# Ornament.net
KiCad netlist of a schematic drawn in Altium Designer
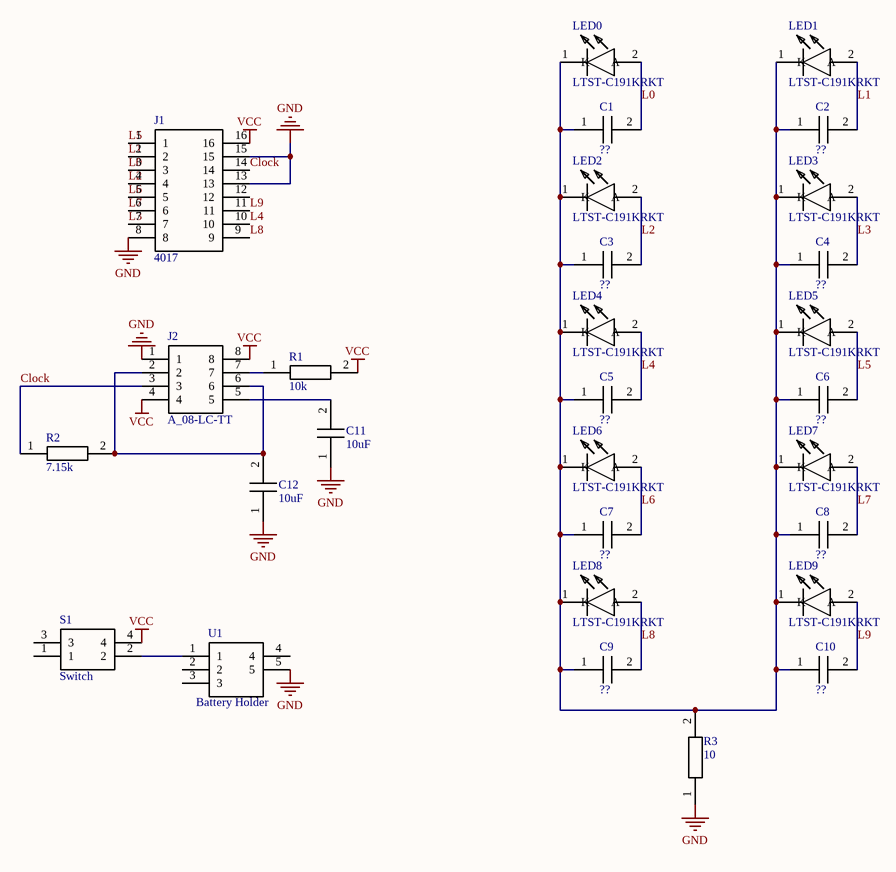
[diagram p0: Ornament.SchDoc]

(export (version "E")
  (design (tool "Eeschema 10.0.6"))
  (components
    (comp (ref "C1")
      (value "??")
      (footprint "SamacSys:CAPC2013X140N")
      (description "Capacitor")
      (fields
        (field (name "MANUFACTURER_PART_NUMBER") "C0805C106K8PACTU")
        (field (name "MOUSER PART NUMBER") "80-C0805C106K8P")
      )
      (libsource (lib "*") (part "C0805C106K8PACTU"))
    )
    (comp (ref "C2")
      (value "??")
      (footprint "SamacSys:CAPC2013X140N")
      (description "Capacitor")
      (fields
        (field (name "MANUFACTURER_PART_NUMBER") "C0805C106K8PACTU")
        (field (name "MOUSER PART NUMBER") "80-C0805C106K8P")
      )
      (libsource (lib "*") (part "C0805C106K8PACTU"))
    )
    (comp (ref "C3")
      (value "??")
      (footprint "SamacSys:CAPC2013X140N")
      (description "Capacitor")
      (fields
        (field (name "MANUFACTURER_PART_NUMBER") "C0805C106K8PACTU")
        (field (name "MOUSER PART NUMBER") "80-C0805C106K8P")
      )
      (libsource (lib "*") (part "C0805C106K8PACTU"))
    )
    (comp (ref "C4")
      (value "??")
      (footprint "SamacSys:CAPC2013X140N")
      (description "Capacitor")
      (fields
        (field (name "MANUFACTURER_PART_NUMBER") "C0805C106K8PACTU")
        (field (name "MOUSER PART NUMBER") "80-C0805C106K8P")
      )
      (libsource (lib "*") (part "C0805C106K8PACTU"))
    )
    (comp (ref "C5")
      (value "??")
      (footprint "SamacSys:CAPC2013X140N")
      (description "Capacitor")
      (fields
        (field (name "MANUFACTURER_PART_NUMBER") "C0805C106K8PACTU")
        (field (name "MOUSER PART NUMBER") "80-C0805C106K8P")
      )
      (libsource (lib "*") (part "C0805C106K8PACTU"))
    )
    (comp (ref "C6")
      (value "??")
      (footprint "SamacSys:CAPC2013X140N")
      (description "Capacitor")
      (fields
        (field (name "MANUFACTURER_PART_NUMBER") "C0805C106K8PACTU")
        (field (name "MOUSER PART NUMBER") "80-C0805C106K8P")
      )
      (libsource (lib "*") (part "C0805C106K8PACTU"))
    )
    (comp (ref "C7")
      (value "??")
      (footprint "SamacSys:CAPC2013X140N")
      (description "Capacitor")
      (fields
        (field (name "MANUFACTURER_PART_NUMBER") "C0805C106K8PACTU")
        (field (name "MOUSER PART NUMBER") "80-C0805C106K8P")
      )
      (libsource (lib "*") (part "C0805C106K8PACTU"))
    )
    (comp (ref "C8")
      (value "??")
      (footprint "SamacSys:CAPC2013X140N")
      (description "Capacitor")
      (fields
        (field (name "MANUFACTURER_PART_NUMBER") "C0805C106K8PACTU")
        (field (name "MOUSER PART NUMBER") "80-C0805C106K8P")
      )
      (libsource (lib "*") (part "C0805C106K8PACTU"))
    )
    (comp (ref "C9")
      (value "??")
      (footprint "SamacSys:CAPC2013X140N")
      (description "Capacitor")
      (fields
        (field (name "MANUFACTURER_PART_NUMBER") "C0805C106K8PACTU")
        (field (name "MOUSER PART NUMBER") "80-C0805C106K8P")
      )
      (libsource (lib "*") (part "C0805C106K8PACTU"))
    )
    (comp (ref "C10")
      (value "??")
      (footprint "SamacSys:CAPC2013X140N")
      (description "Capacitor")
      (fields
        (field (name "MANUFACTURER_PART_NUMBER") "C0805C106K8PACTU")
        (field (name "MOUSER PART NUMBER") "80-C0805C106K8P")
      )
      (libsource (lib "*") (part "C0805C106K8PACTU"))
    )
    (comp (ref "C11")
      (value "10uF")
      (footprint "SamacSys:CAPC2013X140N")
      (description "Capacitor")
      (fields
        (field (name "MANUFACTURER_PART_NUMBER") "C0805C106K8PACTU")
        (field (name "MOUSER PART NUMBER") "80-C0805C106K8P")
      )
      (libsource (lib "*") (part "C0805C106K8PACTU"))
    )
    (comp (ref "C12")
      (value "10uF")
      (footprint "SamacSys:CAPC2013X140N")
      (description "Capacitor")
      (fields
        (field (name "MANUFACTURER_PART_NUMBER") "C0805C106K8PACTU")
        (field (name "MOUSER PART NUMBER") "80-C0805C106K8P")
      )
      (libsource (lib "*") (part "C0805C106K8PACTU"))
    )
    (comp (ref "J1")
      (value "4017")
      (footprint "SamacSys:DIPS762W80P254L2019H533Q16N")
      (description "Connector")
      (fields
        (field (name "MANUFACTURER_PART_NUMBER") "4816-3000-CP")
        (field (name "MOUSER PART NUMBER") "517-4816-3000-CP")
      )
      (libsource (lib "*") (part "4816-3000-CP"))
    )
    (comp (ref "J2")
      (value "A_08-LC-TT")
      (footprint "SamacSys:DIPS762W61P254L1016H525Q8N")
      (description "Connector")
      (fields
        (field (name "MANUFACTURER_PART_NUMBER") "A 08-LC-TT")
        (field (name "RS PART NUMBER") "6742435P")
      )
      (libsource (lib "*") (part "A_08-LC-TT"))
    )
    (comp (ref "LED0")
      (value "LTST-C191KRKT")
      (footprint "SamacSys:LEDC1608X55N")
      (description "LED")
      (fields
        (field (name "MOUSER PART NUMBER") "859-LTST-C191KRKT")
        (field (name "RS PART NUMBER") "1278415P")
      )
      (libsource (lib "*") (part "LTST-C191KRKT"))
    )
    (comp (ref "LED1")
      (value "LTST-C191KRKT")
      (footprint "SamacSys:LEDC1608X55N")
      (description "LED")
      (fields
        (field (name "MOUSER PART NUMBER") "859-LTST-C191KRKT")
        (field (name "RS PART NUMBER") "1278415P")
      )
      (libsource (lib "*") (part "LTST-C191KRKT"))
    )
    (comp (ref "LED2")
      (value "LTST-C191KRKT")
      (footprint "SamacSys:LEDC1608X55N")
      (description "LED")
      (fields
        (field (name "MOUSER PART NUMBER") "859-LTST-C191KRKT")
        (field (name "RS PART NUMBER") "1278415P")
      )
      (libsource (lib "*") (part "LTST-C191KRKT"))
    )
    (comp (ref "LED3")
      (value "LTST-C191KRKT")
      (footprint "SamacSys:LEDC1608X55N")
      (description "LED")
      (fields
        (field (name "MOUSER PART NUMBER") "859-LTST-C191KRKT")
        (field (name "RS PART NUMBER") "1278415P")
      )
      (libsource (lib "*") (part "LTST-C191KRKT"))
    )
    (comp (ref "LED4")
      (value "LTST-C191KRKT")
      (footprint "SamacSys:LEDC1608X55N")
      (description "LED")
      (fields
        (field (name "MOUSER PART NUMBER") "859-LTST-C191KRKT")
        (field (name "RS PART NUMBER") "1278415P")
      )
      (libsource (lib "*") (part "LTST-C191KRKT"))
    )
    (comp (ref "LED5")
      (value "LTST-C191KRKT")
      (footprint "SamacSys:LEDC1608X55N")
      (description "LED")
      (fields
        (field (name "MOUSER PART NUMBER") "859-LTST-C191KRKT")
        (field (name "RS PART NUMBER") "1278415P")
      )
      (libsource (lib "*") (part "LTST-C191KRKT"))
    )
    (comp (ref "LED6")
      (value "LTST-C191KRKT")
      (footprint "SamacSys:LEDC1608X55N")
      (description "LED")
      (fields
        (field (name "MOUSER PART NUMBER") "859-LTST-C191KRKT")
        (field (name "RS PART NUMBER") "1278415P")
      )
      (libsource (lib "*") (part "LTST-C191KRKT"))
    )
    (comp (ref "LED7")
      (value "LTST-C191KRKT")
      (footprint "SamacSys:LEDC1608X55N")
      (description "LED")
      (fields
        (field (name "MOUSER PART NUMBER") "859-LTST-C191KRKT")
        (field (name "RS PART NUMBER") "1278415P")
      )
      (libsource (lib "*") (part "LTST-C191KRKT"))
    )
    (comp (ref "LED8")
      (value "LTST-C191KRKT")
      (footprint "SamacSys:LEDC1608X55N")
      (description "LED")
      (fields
        (field (name "MOUSER PART NUMBER") "859-LTST-C191KRKT")
        (field (name "RS PART NUMBER") "1278415P")
      )
      (libsource (lib "*") (part "LTST-C191KRKT"))
    )
    (comp (ref "LED9")
      (value "LTST-C191KRKT")
      (footprint "SamacSys:LEDC1608X55N")
      (description "LED")
      (fields
        (field (name "MOUSER PART NUMBER") "859-LTST-C191KRKT")
        (field (name "RS PART NUMBER") "1278415P")
      )
      (libsource (lib "*") (part "LTST-C191KRKT"))
    )
    (comp (ref "R1")
      (value "10k")
      (footprint "SamacSys:RESC2012X60N")
      (description "Resistor")
      (fields
        (field (name "MANUFACTURER_PART_NUMBER") "ERA6AEB7151V")
        (field (name "RS PART NUMBER") "7426134")
      )
      (libsource (lib "*") (part "ERA6AEB7151V"))
    )
    (comp (ref "R2")
      (value "7.15k")
      (footprint "SamacSys:RESC2012X60N")
      (description "Resistor")
      (fields
        (field (name "MANUFACTURER_PART_NUMBER") "ERA6AEB7151V")
        (field (name "RS PART NUMBER") "7426134")
      )
      (libsource (lib "*") (part "ERA6AEB7151V"))
    )
    (comp (ref "R3")
      (value "10")
      (footprint "SamacSys:RESC2012X60N")
      (description "Resistor")
      (fields
        (field (name "MANUFACTURER_PART_NUMBER") "ERA6AEB7151V")
        (field (name "RS PART NUMBER") "7426134")
      )
      (libsource (lib "*") (part "ERA6AEB7151V"))
    )
    (comp (ref "S1")
      (value "Switch")
      (footprint "SamacSys:TL3305AF160QG")
      (fields
        (field (name "MANUFACTURER_PART_NUMBER") "TL3305AF160QG")
        (field (name "MOUSER PART NUMBER") "612-TL3305AF160QG")
      )
      (libsource (lib "*") (part "TL3305AF160QG"))
    )
    (comp (ref "U1")
      (value "Battery Holder")
      (footprint "SamacSys:BATHLD001THM")
      (description "Undefined or Miscellaneous")
      (fields
        (field (name "MANUFACTURER_PART_NUMBER") "BAT-HLD-001-THM")
        (field (name "MOUSER PART NUMBER") "712-BAT-HLD-001-THM")
      )
      (libsource (lib "SamacSys") (part "BAT-HLD-001-THM"))
    )
  )
  (nets
    (net (code "1") (name "/Clock") (class "Default")
      (node (ref "J1") (pin "14") (pinfunction "14_14") (pintype "passive"))
      (node (ref "J2") (pin "3") (pinfunction "3_3") (pintype "passive"))
      (node (ref "R2") (pin "1") (pinfunction "1_1") (pintype "passive"))
    )
    (net (code "2") (name "/L0") (class "Default")
      (node (ref "C1") (pin "2") (pinfunction "C2_2") (pintype "passive"))
      (node (ref "J1") (pin "3") (pinfunction "3_3") (pintype "passive"))
      (node (ref "LED0") (pin "2") (pinfunction "A_2") (pintype "passive"))
    )
    (net (code "3") (name "/L1") (class "Default")
      (node (ref "C2") (pin "2") (pinfunction "C2_2") (pintype "passive"))
      (node (ref "J1") (pin "2") (pinfunction "2_2") (pintype "passive"))
      (node (ref "LED1") (pin "2") (pinfunction "A_2") (pintype "passive"))
    )
    (net (code "4") (name "/L2") (class "Default")
      (node (ref "C3") (pin "2") (pinfunction "C2_2") (pintype "passive"))
      (node (ref "J1") (pin "4") (pinfunction "4_4") (pintype "passive"))
      (node (ref "LED2") (pin "2") (pinfunction "A_2") (pintype "passive"))
    )
    (net (code "5") (name "/L3") (class "Default")
      (node (ref "C4") (pin "2") (pinfunction "C2_2") (pintype "passive"))
      (node (ref "J1") (pin "7") (pinfunction "7_7") (pintype "passive"))
      (node (ref "LED3") (pin "2") (pinfunction "A_2") (pintype "passive"))
    )
    (net (code "6") (name "/L4") (class "Default")
      (node (ref "C5") (pin "2") (pinfunction "C2_2") (pintype "passive"))
      (node (ref "J1") (pin "10") (pinfunction "10_10") (pintype "passive"))
      (node (ref "LED4") (pin "2") (pinfunction "A_2") (pintype "passive"))
    )
    (net (code "7") (name "/L5") (class "Default")
      (node (ref "C6") (pin "2") (pinfunction "C2_2") (pintype "passive"))
      (node (ref "J1") (pin "1") (pinfunction "1_1") (pintype "passive"))
      (node (ref "LED5") (pin "2") (pinfunction "A_2") (pintype "passive"))
    )
    (net (code "8") (name "/L6") (class "Default")
      (node (ref "C7") (pin "2") (pinfunction "C2_2") (pintype "passive"))
      (node (ref "J1") (pin "5") (pinfunction "5_5") (pintype "passive"))
      (node (ref "LED6") (pin "2") (pinfunction "A_2") (pintype "passive"))
    )
    (net (code "9") (name "/L7") (class "Default")
      (node (ref "C8") (pin "2") (pinfunction "C2_2") (pintype "passive"))
      (node (ref "J1") (pin "6") (pinfunction "6_6") (pintype "passive"))
      (node (ref "LED7") (pin "2") (pinfunction "A_2") (pintype "passive"))
    )
    (net (code "10") (name "/L8") (class "Default")
      (node (ref "C9") (pin "2") (pinfunction "C2_2") (pintype "passive"))
      (node (ref "J1") (pin "9") (pinfunction "9_9") (pintype "passive"))
      (node (ref "LED8") (pin "2") (pinfunction "A_2") (pintype "passive"))
    )
    (net (code "11") (name "/L9") (class "Default")
      (node (ref "C10") (pin "2") (pinfunction "C2_2") (pintype "passive"))
      (node (ref "J1") (pin "11") (pinfunction "11_11") (pintype "passive"))
      (node (ref "LED9") (pin "2") (pinfunction "A_2") (pintype "passive"))
    )
    (net (code "12") (name "GND") (class "Default")
      (node (ref "C11") (pin "1") (pinfunction "C1_1") (pintype "passive"))
      (node (ref "C12") (pin "1") (pinfunction "C1_1") (pintype "passive"))
      (node (ref "J1") (pin "13") (pinfunction "13_13") (pintype "passive"))
      (node (ref "J1") (pin "15") (pinfunction "15_15") (pintype "passive"))
      (node (ref "J1") (pin "8") (pinfunction "8_8") (pintype "passive"))
      (node (ref "J2") (pin "1") (pinfunction "1_1") (pintype "passive"))
      (node (ref "R3") (pin "1") (pinfunction "1_1") (pintype "passive"))
      (node (ref "U1") (pin "5") (pinfunction "5_5") (pintype "passive"))
    )
    (net (code "13") (name "Net-(C1-C1)") (class "Default")
      (node (ref "C1") (pin "1") (pinfunction "C1_1") (pintype "passive"))
      (node (ref "C10") (pin "1") (pinfunction "C1_1") (pintype "passive"))
      (node (ref "C2") (pin "1") (pinfunction "C1_1") (pintype "passive"))
      (node (ref "C3") (pin "1") (pinfunction "C1_1") (pintype "passive"))
      (node (ref "C4") (pin "1") (pinfunction "C1_1") (pintype "passive"))
      (node (ref "C5") (pin "1") (pinfunction "C1_1") (pintype "passive"))
      (node (ref "C6") (pin "1") (pinfunction "C1_1") (pintype "passive"))
      (node (ref "C7") (pin "1") (pinfunction "C1_1") (pintype "passive"))
      (node (ref "C8") (pin "1") (pinfunction "C1_1") (pintype "passive"))
      (node (ref "C9") (pin "1") (pinfunction "C1_1") (pintype "passive"))
      (node (ref "LED0") (pin "1") (pinfunction "K_1") (pintype "passive"))
      (node (ref "LED1") (pin "1") (pinfunction "K_1") (pintype "passive"))
      (node (ref "LED2") (pin "1") (pinfunction "K_1") (pintype "passive"))
      (node (ref "LED3") (pin "1") (pinfunction "K_1") (pintype "passive"))
      (node (ref "LED4") (pin "1") (pinfunction "K_1") (pintype "passive"))
      (node (ref "LED5") (pin "1") (pinfunction "K_1") (pintype "passive"))
      (node (ref "LED6") (pin "1") (pinfunction "K_1") (pintype "passive"))
      (node (ref "LED7") (pin "1") (pinfunction "K_1") (pintype "passive"))
      (node (ref "LED8") (pin "1") (pinfunction "K_1") (pintype "passive"))
      (node (ref "LED9") (pin "1") (pinfunction "K_1") (pintype "passive"))
      (node (ref "R3") (pin "2") (pinfunction "2_2") (pintype "passive"))
    )
    (net (code "14") (name "Net-(C11-C2)") (class "Default")
      (node (ref "C11") (pin "2") (pinfunction "C2_2") (pintype "passive"))
      (node (ref "J2") (pin "5") (pinfunction "5_5") (pintype "passive"))
    )
    (net (code "15") (name "Net-(C12-C2)") (class "Default")
      (node (ref "C12") (pin "2") (pinfunction "C2_2") (pintype "passive"))
      (node (ref "J2") (pin "2") (pinfunction "2_2") (pintype "passive"))
      (node (ref "J2") (pin "6") (pinfunction "6_6") (pintype "passive"))
      (node (ref "R2") (pin "2") (pinfunction "2_2") (pintype "passive"))
    )
    (net (code "16") (name "Net-(J2-Pad7)") (class "Default")
      (node (ref "J2") (pin "7") (pinfunction "7_7") (pintype "passive"))
      (node (ref "R1") (pin "1") (pinfunction "1_1") (pintype "passive"))
    )
    (net (code "17") (name "Net-(S1-Pad2)") (class "Default")
      (node (ref "S1") (pin "2") (pinfunction "2_2") (pintype "passive"))
      (node (ref "U1") (pin "1") (pinfunction "1_1") (pintype "passive"))
    )
    (net (code "18") (name "VCC") (class "Default")
      (node (ref "J1") (pin "16") (pinfunction "16_16") (pintype "passive"))
      (node (ref "J2") (pin "4") (pinfunction "4_4") (pintype "passive"))
      (node (ref "J2") (pin "8") (pinfunction "8_8") (pintype "passive"))
      (node (ref "R1") (pin "2") (pinfunction "2_2") (pintype "passive"))
      (node (ref "S1") (pin "4") (pinfunction "4_4") (pintype "passive"))
    )
    (net (code "19") (name "unconnected-(J1-Pad12)") (class "Default")
      (node (ref "J1") (pin "12") (pinfunction "12_12") (pintype "passive"))
    )
    (net (code "20") (name "unconnected-(S1-Pad1)") (class "Default")
      (node (ref "S1") (pin "1") (pinfunction "1_1") (pintype "passive"))
    )
    (net (code "21") (name "unconnected-(S1-Pad3)") (class "Default")
      (node (ref "S1") (pin "3") (pinfunction "3_3") (pintype "passive"))
    )
    (net (code "22") (name "unconnected-(U1-Pad2)") (class "Default")
      (node (ref "U1") (pin "2") (pinfunction "2_2") (pintype "passive"))
    )
    (net (code "23") (name "unconnected-(U1-Pad3)") (class "Default")
      (node (ref "U1") (pin "3") (pinfunction "3_3") (pintype "passive"))
    )
    (net (code "24") (name "unconnected-(U1-Pad4)") (class "Default")
      (node (ref "U1") (pin "4") (pinfunction "4_4") (pintype "passive"))
    )
  )
)
